# AudioLab.net
KiCad netlist of a schematic drawn in Altium Designer
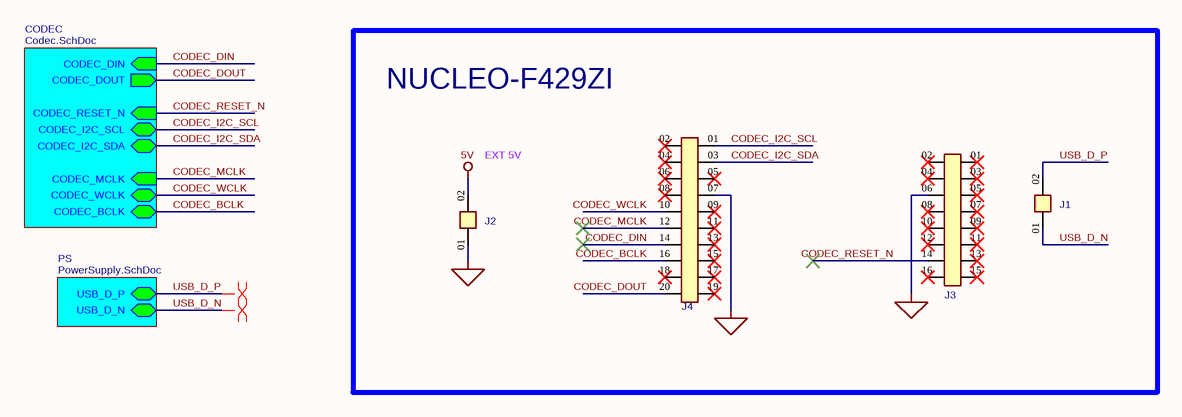
[diagram p0: AudioLab.SchDoc]

(export (version "E")
  (design (tool "Eeschema 10.0.6"))
  (components
    (comp (ref "J1")
      (value "HTSW-102-07-G-S")
      (footprint "SAMTEC_HTSW-102-XX-X-S")
      (description "Pin Header, Vertical, Board-to-Board, 2.54 mm, 1 Rows, 2 Contacts, Through Hole, HTSW")
      (fields (field (name "MANUFACTURER") "Samtec Inc."))
      (libsource (lib "Connectors") (part "HTSW-102-07-G-S"))
    )
    (comp (ref "J2")
      (value "HTSW-102-07-G-S")
      (footprint "SAMTEC_HTSW-102-XX-X-S")
      (description "Pin Header, Vertical, Board-to-Board, 2.54 mm, 1 Rows, 2 Contacts, Through Hole, HTSW")
      (fields (field (name "MANUFACTURER") "Samtec Inc."))
      (libsource (lib "Connectors") (part "HTSW-102-07-G-S"))
    )
    (comp (ref "J3")
      (value "TSW-108-07-G-D")
      (footprint "SAMTEC_TSW-108-07-G-D")
      (description "Pin Header, Unshrouded, Board-to-Board, 2.54 mm, 2 Rows, 16 Contacts, Through Hole, TSW")
      (fields (field (name "MANUFACTURER") "Samtec Inc."))
      (libsource (lib "Connectors") (part "TSW-108-07-G-D"))
    )
    (comp (ref "J4")
      (value "TSW-110-07-G-D")
      (footprint "SAMTEC_TSW-110-07-G-D")
      (description "Pin Header, Vertical, Board-to-Board, 2.54 mm, 2 Rows, 20 Contacts, Through Hole, HTSW Series")
      (fields (field (name "MANUFACTURER") "Samtec Inc."))
      (libsource (lib "Connectors") (part "TSW-110-07-G-D"))
    )
  )
  (nets
    (net (code "1") (name "/CODEC_BCLK") (class "Default")
      (node (ref "J4") (pin "16") (pinfunction "16_16") (pintype "passive"))
    )
    (net (code "2") (name "/CODEC_DIN") (class "Default")
      (node (ref "J4") (pin "14") (pinfunction "14_14") (pintype "passive+no_connect"))
    )
    (net (code "3") (name "/CODEC_DOUT") (class "Default")
      (node (ref "J4") (pin "20") (pinfunction "20_20") (pintype "passive"))
    )
    (net (code "4") (name "/CODEC_I2C_SCL") (class "Default")
      (node (ref "J4") (pin "01") (pinfunction "01_01") (pintype "passive"))
    )
    (net (code "5") (name "/CODEC_I2C_SDA") (class "Default")
      (node (ref "J4") (pin "03") (pinfunction "03_03") (pintype "passive"))
    )
    (net (code "6") (name "/CODEC_MCLK") (class "Default")
      (node (ref "J4") (pin "12") (pinfunction "12_12") (pintype "passive+no_connect"))
    )
    (net (code "7") (name "/CODEC_RESET_N") (class "Default")
      (node (ref "J3") (pin "14") (pinfunction "14_14") (pintype "passive+no_connect"))
    )
    (net (code "8") (name "/CODEC_WCLK") (class "Default")
      (node (ref "J4") (pin "10") (pinfunction "10_10") (pintype "passive"))
    )
    (net (code "9") (name "/USB_D_N") (class "Default")
      (node (ref "J1") (pin "01") (pinfunction "01_01") (pintype "passive"))
    )
    (net (code "10") (name "/USB_D_P") (class "Default")
      (node (ref "J1") (pin "02") (pinfunction "02_02") (pintype "passive"))
    )
    (net (code "11") (name "5V") (class "Default")
      (node (ref "J2") (pin "02") (pinfunction "02_02") (pintype "passive"))
    )
    (net (code "12") (name "GND") (class "Default")
      (node (ref "J2") (pin "01") (pinfunction "01_01") (pintype "passive"))
      (node (ref "J3") (pin "06") (pinfunction "06_06") (pintype "passive"))
      (node (ref "J4") (pin "07") (pinfunction "07_07") (pintype "passive"))
    )
    (net (code "13") (name "unconnected-(J3-Pad01)") (class "Default")
      (node (ref "J3") (pin "01") (pinfunction "01_01") (pintype "passive+no_connect"))
    )
    (net (code "14") (name "unconnected-(J3-Pad02)") (class "Default")
      (node (ref "J3") (pin "02") (pinfunction "02_02") (pintype "passive+no_connect"))
    )
    (net (code "15") (name "unconnected-(J3-Pad03)") (class "Default")
      (node (ref "J3") (pin "03") (pinfunction "03_03") (pintype "passive+no_connect"))
    )
    (net (code "16") (name "unconnected-(J3-Pad04)") (class "Default")
      (node (ref "J3") (pin "04") (pinfunction "04_04") (pintype "passive+no_connect"))
    )
    (net (code "17") (name "unconnected-(J3-Pad05)") (class "Default")
      (node (ref "J3") (pin "05") (pinfunction "05_05") (pintype "passive+no_connect"))
    )
    (net (code "18") (name "unconnected-(J3-Pad07)") (class "Default")
      (node (ref "J3") (pin "07") (pinfunction "07_07") (pintype "passive+no_connect"))
    )
    (net (code "19") (name "unconnected-(J3-Pad08)") (class "Default")
      (node (ref "J3") (pin "08") (pinfunction "08_08") (pintype "passive+no_connect"))
    )
    (net (code "20") (name "unconnected-(J3-Pad09)") (class "Default")
      (node (ref "J3") (pin "09") (pinfunction "09_09") (pintype "passive+no_connect"))
    )
    (net (code "21") (name "unconnected-(J3-Pad10)") (class "Default")
      (node (ref "J3") (pin "10") (pinfunction "10_10") (pintype "passive+no_connect"))
    )
    (net (code "22") (name "unconnected-(J3-Pad11)") (class "Default")
      (node (ref "J3") (pin "11") (pinfunction "11_11") (pintype "passive+no_connect"))
    )
    (net (code "23") (name "unconnected-(J3-Pad12)") (class "Default")
      (node (ref "J3") (pin "12") (pinfunction "12_12") (pintype "passive+no_connect"))
    )
    (net (code "24") (name "unconnected-(J3-Pad13)") (class "Default")
      (node (ref "J3") (pin "13") (pinfunction "13_13") (pintype "passive+no_connect"))
    )
    (net (code "25") (name "unconnected-(J3-Pad15)") (class "Default")
      (node (ref "J3") (pin "15") (pinfunction "15_15") (pintype "passive+no_connect"))
    )
    (net (code "26") (name "unconnected-(J3-Pad16)") (class "Default")
      (node (ref "J3") (pin "16") (pinfunction "16_16") (pintype "passive+no_connect"))
    )
    (net (code "27") (name "unconnected-(J4-Pad02)") (class "Default")
      (node (ref "J4") (pin "02") (pinfunction "02_02") (pintype "passive+no_connect"))
    )
    (net (code "28") (name "unconnected-(J4-Pad04)") (class "Default")
      (node (ref "J4") (pin "04") (pinfunction "04_04") (pintype "passive+no_connect"))
    )
    (net (code "29") (name "unconnected-(J4-Pad05)") (class "Default")
      (node (ref "J4") (pin "05") (pinfunction "05_05") (pintype "passive+no_connect"))
    )
    (net (code "30") (name "unconnected-(J4-Pad06)") (class "Default")
      (node (ref "J4") (pin "06") (pinfunction "06_06") (pintype "passive+no_connect"))
    )
    (net (code "31") (name "unconnected-(J4-Pad08)") (class "Default")
      (node (ref "J4") (pin "08") (pinfunction "08_08") (pintype "passive+no_connect"))
    )
    (net (code "32") (name "unconnected-(J4-Pad09)") (class "Default")
      (node (ref "J4") (pin "09") (pinfunction "09_09") (pintype "passive+no_connect"))
    )
    (net (code "33") (name "unconnected-(J4-Pad11)") (class "Default")
      (node (ref "J4") (pin "11") (pinfunction "11_11") (pintype "passive+no_connect"))
    )
    (net (code "34") (name "unconnected-(J4-Pad13)") (class "Default")
      (node (ref "J4") (pin "13") (pinfunction "13_13") (pintype "passive+no_connect"))
    )
    (net (code "35") (name "unconnected-(J4-Pad15)") (class "Default")
      (node (ref "J4") (pin "15") (pinfunction "15_15") (pintype "passive+no_connect"))
    )
    (net (code "36") (name "unconnected-(J4-Pad17)") (class "Default")
      (node (ref "J4") (pin "17") (pinfunction "17_17") (pintype "passive+no_connect"))
    )
    (net (code "37") (name "unconnected-(J4-Pad18)") (class "Default")
      (node (ref "J4") (pin "18") (pinfunction "18_18") (pintype "passive+no_connect"))
    )
    (net (code "38") (name "unconnected-(J4-Pad19)") (class "Default")
      (node (ref "J4") (pin "19") (pinfunction "19_19") (pintype "passive+no_connect"))
    )
  )
)
